# BV100011_ControlRS485.net
KiCad netlist of a schematic drawn in Altium Designer
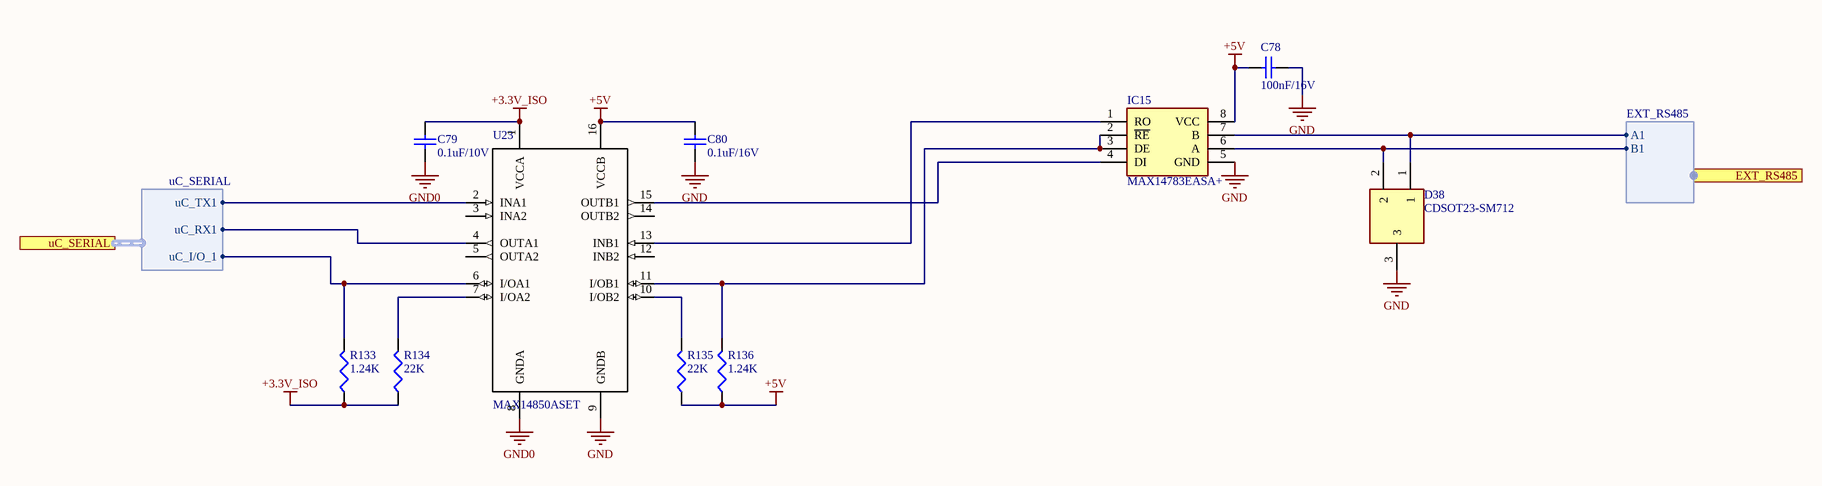
[diagram p0: BV100011_ControlRS485.SchDoc]

(export (version "E")
  (design (tool "Eeschema 10.0.6"))
  (components
    (comp (ref "C78")
      (value "100nF/16V")
      (footprint "C1206")
      (description "Capacitor (Semiconductor SIM Model)")
      (fields (field (name "PUBLISHER") "Altium Limited"))
      (libsource (lib "Miscellaneous Devices") (part "Cap Semi"))
    )
    (comp (ref "C79")
      (value "0.1uF/10V")
      (footprint "C1206")
      (description "Capacitor (Semiconductor SIM Model)")
      (fields (field (name "PUBLISHER") "Altium Limited"))
      (libsource (lib "Miscellaneous Devices") (part "Cap Semi"))
    )
    (comp (ref "C80")
      (value "0.1uF/16V")
      (footprint "C1206")
      (description "Capacitor (Semiconductor SIM Model)")
      (fields (field (name "PUBLISHER") "Altium Limited"))
      (libsource (lib "Miscellaneous Devices") (part "Cap Semi"))
    )
    (comp (ref "D38")
      (value "CDSOT23-SM712")
      (footprint "SOT95P230X117-3N")
      (description "Diode")
      (fields
        (field (name "MOUSER PART NUMBER") "652-CDSOT23-SM712")
        (field (name "RS PART NUMBER") "7673728P")
      )
      (libsource (lib "SM712") (part "CDSOT23-SM712"))
    )
    (comp (ref "IC15")
      (value "MAX14783EASA+")
      (footprint "SOIC127P600X175-8N")
      (description "Integrated Circuit")
      (fields (field (name "MOUSER PART NUMBER") "700-MAX14783EASA+"))
      (libsource (lib "MAX14783EASA+") (part "MAX14783EASA+"))
    )
    (comp (ref "R133")
      (value "1.24K")
      (footprint "J1-0603")
      (description "Resistor")
      (fields (field (name "PUBLISHER") "Altium Limited"))
      (libsource (lib "Miscellaneous Devices") (part "Res3"))
    )
    (comp (ref "R134")
      (value "22K")
      (footprint "J1-0603")
      (description "Resistor")
      (fields (field (name "PUBLISHER") "Altium Limited"))
      (libsource (lib "Miscellaneous Devices") (part "Res3"))
    )
    (comp (ref "R135")
      (value "22K")
      (footprint "C1206")
      (description "Resistor")
      (fields (field (name "PUBLISHER") "Altium Limited"))
      (libsource (lib "Miscellaneous Devices") (part "Res3"))
    )
    (comp (ref "R136")
      (value "1.24K")
      (footprint "C1206")
      (description "Resistor")
      (fields (field (name "PUBLISHER") "Altium Limited"))
      (libsource (lib "Miscellaneous Devices") (part "Res3"))
    )
    (comp (ref "U23")
      (value "MAX14850ASET")
      (footprint "*SOIC127P600X175-16N")
      (description "Digital Isolator, 6-Ch, 30ns, Nsoic-16")
      (fields (field (name "MF") "Maxim Integrated") (field (name "MP") "MAX14850ASE+"))
      (libsource (lib "MAX14850ASET") (part "MAX14850ASET"))
    )
  )
  (nets
    (net (code "3") (name "+3.3V_ISO") (class "Default")
      (node (ref "C79") (pin "1") (pinfunction "1_1") (pintype "passive"))
      (node (ref "R133") (pin "1") (pinfunction "1_1") (pintype "passive"))
      (node (ref "R134") (pin "1") (pinfunction "1_1") (pintype "passive"))
      (node (ref "U23") (pin "1") (pinfunction "VCCA_1") (pintype "power_in"))
    )
    (net (code "4") (name "+5V") (class "Default")
      (node (ref "C78") (pin "1") (pinfunction "1_1") (pintype "passive"))
      (node (ref "C80") (pin "1") (pinfunction "1_1") (pintype "passive"))
      (node (ref "IC15") (pin "8") (pinfunction "VCC_8") (pintype "passive"))
      (node (ref "R135") (pin "1") (pinfunction "1_1") (pintype "passive"))
      (node (ref "R136") (pin "1") (pinfunction "1_1") (pintype "passive"))
      (node (ref "U23") (pin "16") (pinfunction "VCCB_16") (pintype "power_in"))
    )
    (net (code "5") (name "/A1") (class "Default")
      (node (ref "D38") (pin "1") (pinfunction "1_1") (pintype "passive"))
      (node (ref "IC15") (pin "7") (pinfunction "B_7") (pintype "passive"))
    )
    (net (code "6") (name "/B1") (class "Default")
      (node (ref "D38") (pin "2") (pinfunction "2_2") (pintype "passive"))
      (node (ref "IC15") (pin "6") (pinfunction "A_6") (pintype "passive"))
    )
    (net (code "7") (name "/uC_I{slash}O_1") (class "Default")
      (node (ref "R133") (pin "2") (pinfunction "2_2") (pintype "passive"))
      (node (ref "U23") (pin "6") (pinfunction "I/OA1_6") (pintype "bidirectional"))
    )
    (net (code "8") (name "/uC_RX1") (class "Default")
      (node (ref "U23") (pin "4") (pinfunction "OUTA1_4") (pintype "output"))
    )
    (net (code "9") (name "/uC_TX1") (class "Default")
      (node (ref "U23") (pin "2") (pinfunction "INA1_2") (pintype "input"))
    )
    (net (code "12") (name "GND") (class "Default")
      (node (ref "C78") (pin "2") (pinfunction "2_2") (pintype "passive"))
      (node (ref "C80") (pin "2") (pinfunction "2_2") (pintype "passive"))
      (node (ref "D38") (pin "3") (pinfunction "3_3") (pintype "passive"))
      (node (ref "IC15") (pin "5") (pinfunction "GND_5") (pintype "passive"))
      (node (ref "U23") (pin "9") (pinfunction "GNDB_9") (pintype "power_in"))
    )
    (net (code "13") (name "GND0") (class "Default")
      (node (ref "C79") (pin "2") (pinfunction "2_2") (pintype "passive"))
      (node (ref "U23") (pin "8") (pinfunction "GNDA_8") (pintype "power_in"))
    )
    (net (code "14") (name "Net-(IC15-DE)") (class "Default")
      (node (ref "IC15") (pin "2") (pinfunction "~{RE}_2") (pintype "passive"))
      (node (ref "IC15") (pin "3") (pinfunction "DE_3") (pintype "passive"))
      (node (ref "R136") (pin "2") (pinfunction "2_2") (pintype "passive"))
      (node (ref "U23") (pin "11") (pinfunction "I/OB1_11") (pintype "bidirectional"))
    )
    (net (code "15") (name "Net-(IC15-DI)") (class "Default")
      (node (ref "IC15") (pin "4") (pinfunction "DI_4") (pintype "passive"))
      (node (ref "U23") (pin "15") (pinfunction "OUTB1_15") (pintype "output"))
    )
    (net (code "16") (name "Net-(IC15-RO)") (class "Default")
      (node (ref "IC15") (pin "1") (pinfunction "RO_1") (pintype "passive"))
      (node (ref "U23") (pin "13") (pinfunction "INB1_13") (pintype "input"))
    )
    (net (code "17") (name "Net-(U23-I{slash}OA2)") (class "Default")
      (node (ref "R134") (pin "2") (pinfunction "2_2") (pintype "passive"))
      (node (ref "U23") (pin "7") (pinfunction "I/OA2_7") (pintype "bidirectional"))
    )
    (net (code "18") (name "Net-(U23-I{slash}OB2)") (class "Default")
      (node (ref "R135") (pin "2") (pinfunction "2_2") (pintype "passive"))
      (node (ref "U23") (pin "10") (pinfunction "I/OB2_10") (pintype "bidirectional"))
    )
    (net (code "19") (name "unconnected-(U23-INA2-Pad3)") (class "Default")
      (node (ref "U23") (pin "3") (pinfunction "INA2_3") (pintype "input"))
    )
    (net (code "20") (name "unconnected-(U23-INB2-Pad12)") (class "Default")
      (node (ref "U23") (pin "12") (pinfunction "INB2_12") (pintype "input"))
    )
    (net (code "21") (name "unconnected-(U23-OUTA2-Pad5)") (class "Default")
      (node (ref "U23") (pin "5") (pinfunction "OUTA2_5") (pintype "output"))
    )
    (net (code "22") (name "unconnected-(U23-OUTB2-Pad14)") (class "Default")
      (node (ref "U23") (pin "14") (pinfunction "OUTB2_14") (pintype "output"))
    )
  )
)
